# 00.net
KiCad netlist of a schematic drawn in Altium Designer
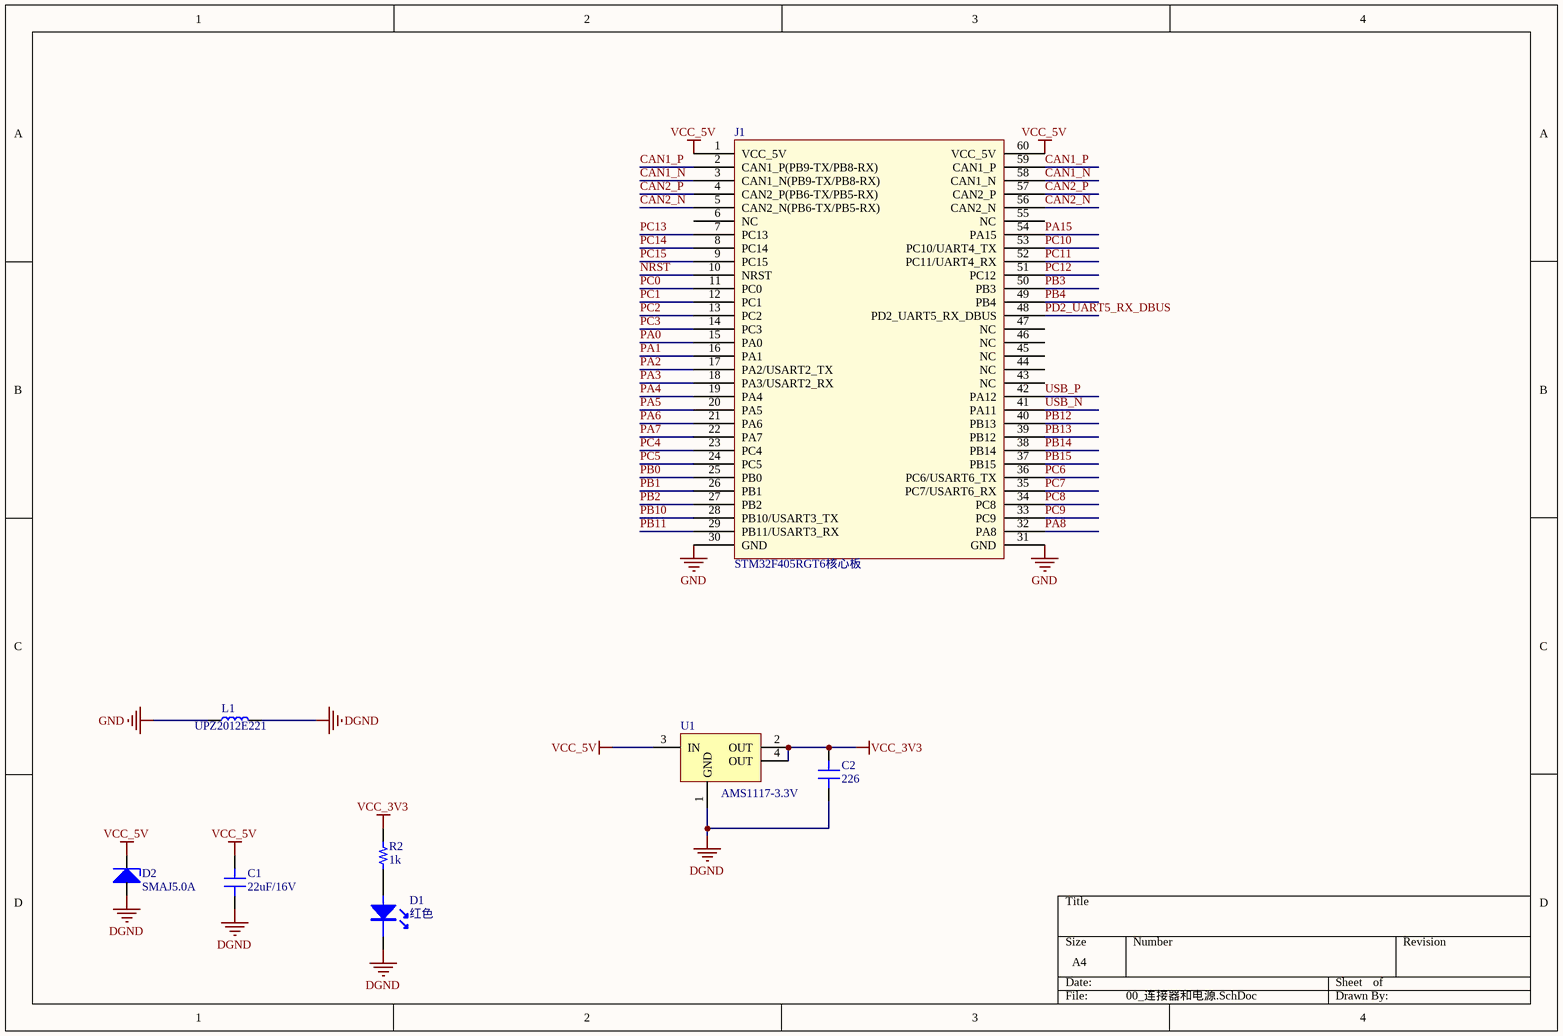
[diagram p0: 00_连接器和电源.SchDoc]

(export (version "E")
  (design (tool "Eeschema 10.0.6"))
  (components
    (comp (ref "C1")
      (value "22uF/16V")
      (footprint "C1206/3216")
      (description "陶瓷电容")
      (libsource (lib "WMJ2019_Devices") (part "陶瓷电容"))
    )
    (comp (ref "C2")
      (value "226")
      (footprint "C0603/1608")
      (description "陶瓷电容")
      (libsource (lib "WMJ2019_Devices") (part "陶瓷电容"))
    )
    (comp (ref "D1")
      (value "LED-红色")
      (footprint "LED0603-红色")
      (description "发光二极管")
      (fields (field (name "COLOR") "红色"))
      (libsource (lib "WMJ2019_Devices") (part "LED"))
    )
    (comp (ref "D2")
      (value "SMAJ5.0A")
      (footprint "DO-214AC/SMA")
      (description "瞬态抑制二极管")
      (libsource (lib "WMJ2019_Devices") (part "瞬态抑制二极管"))
    )
    (comp (ref "J1")
      (value "STM32F405RGT6核心板")
      (footprint "3710M060037G0FR01")
      (description "3710(F/M)060037G0FR01")
      (libsource (lib "Connectors") (part "STM32F405RGT6核心板"))
    )
    (comp (ref "L1")
      (value "UPZ2012E221")
      (footprint "L0805/2012")
      (description "贴片磁珠")
      (libsource (lib "WMJ2019_Devices") (part "磁珠"))
    )
    (comp (ref "R2")
      (value "1k")
      (footprint "R0603/1608")
      (description "电阻")
      (libsource (lib "WMJ2019_Devices") (part "电阻"))
    )
    (comp (ref "U1")
      (value "AMS1117-3.3V")
      (footprint "SOT-223")
      (description "AMS1117低压差线性稳压器")
      (libsource (lib "WMJ2019_Devices") (part "AMS1117"))
    )
  )
  (nets
    (net (code "1") (name "/CAN1_N") (class "Default")
      (node (ref "J1") (pin "3") (pinfunction "CAN1_N(PB9-TX/PB8-RX)_3") (pintype "passive"))
      (node (ref "J1") (pin "58") (pinfunction "CAN1_N_58") (pintype "passive"))
    )
    (net (code "2") (name "/CAN1_P") (class "Default")
      (node (ref "J1") (pin "2") (pinfunction "CAN1_P(PB9-TX/PB8-RX)_2") (pintype "passive"))
      (node (ref "J1") (pin "59") (pinfunction "CAN1_P_59") (pintype "passive"))
    )
    (net (code "3") (name "/CAN2_N") (class "Default")
      (node (ref "J1") (pin "5") (pinfunction "CAN2_N(PB6-TX/PB5-RX)_5") (pintype "passive"))
      (node (ref "J1") (pin "56") (pinfunction "CAN2_N_56") (pintype "passive"))
    )
    (net (code "4") (name "/CAN2_P") (class "Default")
      (node (ref "J1") (pin "4") (pinfunction "CAN2_P(PB6-TX/PB5-RX)_4") (pintype "passive"))
      (node (ref "J1") (pin "57") (pinfunction "CAN2_P_57") (pintype "passive"))
    )
    (net (code "5") (name "/NRST") (class "Default")
      (node (ref "J1") (pin "10") (pinfunction "NRST_10") (pintype "passive"))
    )
    (net (code "6") (name "/PA0") (class "Default")
      (node (ref "J1") (pin "15") (pinfunction "PA0_15") (pintype "passive"))
    )
    (net (code "7") (name "/PA1") (class "Default")
      (node (ref "J1") (pin "16") (pinfunction "PA1_16") (pintype "passive"))
    )
    (net (code "8") (name "/PA2") (class "Default")
      (node (ref "J1") (pin "17") (pinfunction "PA2/USART2_TX_17") (pintype "passive"))
    )
    (net (code "9") (name "/PA3") (class "Default")
      (node (ref "J1") (pin "18") (pinfunction "PA3/USART2_RX_18") (pintype "passive"))
    )
    (net (code "10") (name "/PA4") (class "Default")
      (node (ref "J1") (pin "19") (pinfunction "PA4_19") (pintype "passive"))
    )
    (net (code "11") (name "/PA5") (class "Default")
      (node (ref "J1") (pin "20") (pinfunction "PA5_20") (pintype "passive"))
    )
    (net (code "12") (name "/PA6") (class "Default")
      (node (ref "J1") (pin "21") (pinfunction "PA6_21") (pintype "passive"))
    )
    (net (code "13") (name "/PA7") (class "Default")
      (node (ref "J1") (pin "22") (pinfunction "PA7_22") (pintype "passive"))
    )
    (net (code "14") (name "/PA8") (class "Default")
      (node (ref "J1") (pin "32") (pinfunction "PA8_32") (pintype "passive"))
    )
    (net (code "15") (name "/PA15") (class "Default")
      (node (ref "J1") (pin "54") (pinfunction "PA15_54") (pintype "passive"))
    )
    (net (code "16") (name "/PB0") (class "Default")
      (node (ref "J1") (pin "25") (pinfunction "PB0_25") (pintype "passive"))
    )
    (net (code "17") (name "/PB1") (class "Default")
      (node (ref "J1") (pin "26") (pinfunction "PB1_26") (pintype "passive"))
    )
    (net (code "18") (name "/PB2") (class "Default")
      (node (ref "J1") (pin "27") (pinfunction "PB2_27") (pintype "passive"))
    )
    (net (code "19") (name "/PB3") (class "Default")
      (node (ref "J1") (pin "50") (pinfunction "PB3_50") (pintype "passive"))
    )
    (net (code "20") (name "/PB4") (class "Default")
      (node (ref "J1") (pin "49") (pinfunction "PB4_49") (pintype "passive"))
    )
    (net (code "21") (name "/PB10") (class "Default")
      (node (ref "J1") (pin "28") (pinfunction "PB10/USART3_TX_28") (pintype "passive"))
    )
    (net (code "22") (name "/PB11") (class "Default")
      (node (ref "J1") (pin "29") (pinfunction "PB11/USART3_RX_29") (pintype "passive"))
    )
    (net (code "23") (name "/PB12") (class "Default")
      (node (ref "J1") (pin "40") (pinfunction "PB13_40") (pintype "passive"))
    )
    (net (code "24") (name "/PB13") (class "Default")
      (node (ref "J1") (pin "39") (pinfunction "PB12_39") (pintype "passive"))
    )
    (net (code "25") (name "/PB14") (class "Default")
      (node (ref "J1") (pin "38") (pinfunction "PB14_38") (pintype "passive"))
    )
    (net (code "26") (name "/PB15") (class "Default")
      (node (ref "J1") (pin "37") (pinfunction "PB15_37") (pintype "passive"))
    )
    (net (code "27") (name "/PC0") (class "Default")
      (node (ref "J1") (pin "11") (pinfunction "PC0_11") (pintype "passive"))
    )
    (net (code "28") (name "/PC1") (class "Default")
      (node (ref "J1") (pin "12") (pinfunction "PC1_12") (pintype "passive"))
    )
    (net (code "29") (name "/PC2") (class "Default")
      (node (ref "J1") (pin "13") (pinfunction "PC2_13") (pintype "passive"))
    )
    (net (code "30") (name "/PC3") (class "Default")
      (node (ref "J1") (pin "14") (pinfunction "PC3_14") (pintype "passive"))
    )
    (net (code "31") (name "/PC4") (class "Default")
      (node (ref "J1") (pin "23") (pinfunction "PC4_23") (pintype "passive"))
    )
    (net (code "32") (name "/PC5") (class "Default")
      (node (ref "J1") (pin "24") (pinfunction "PC5_24") (pintype "passive"))
    )
    (net (code "33") (name "/PC6") (class "Default")
      (node (ref "J1") (pin "36") (pinfunction "PC6/USART6_TX_36") (pintype "passive"))
    )
    (net (code "34") (name "/PC7") (class "Default")
      (node (ref "J1") (pin "35") (pinfunction "PC7/USART6_RX_35") (pintype "passive"))
    )
    (net (code "35") (name "/PC8") (class "Default")
      (node (ref "J1") (pin "34") (pinfunction "PC8_34") (pintype "passive"))
    )
    (net (code "36") (name "/PC9") (class "Default")
      (node (ref "J1") (pin "33") (pinfunction "PC9_33") (pintype "passive"))
    )
    (net (code "37") (name "/PC10") (class "Default")
      (node (ref "J1") (pin "53") (pinfunction "PC10/UART4_TX_53") (pintype "passive"))
    )
    (net (code "38") (name "/PC11") (class "Default")
      (node (ref "J1") (pin "52") (pinfunction "PC11/UART4_RX_52") (pintype "passive"))
    )
    (net (code "39") (name "/PC12") (class "Default")
      (node (ref "J1") (pin "51") (pinfunction "PC12_51") (pintype "passive"))
    )
    (net (code "40") (name "/PC13") (class "Default")
      (node (ref "J1") (pin "7") (pinfunction "PC13_7") (pintype "passive"))
    )
    (net (code "41") (name "/PC14") (class "Default")
      (node (ref "J1") (pin "8") (pinfunction "PC14_8") (pintype "passive"))
    )
    (net (code "42") (name "/PC15") (class "Default")
      (node (ref "J1") (pin "9") (pinfunction "PC15_9") (pintype "passive"))
    )
    (net (code "43") (name "/PD2_UART5_RX_DBUS") (class "Default")
      (node (ref "J1") (pin "48") (pinfunction "PD2_UART5_RX_DBUS_48") (pintype "passive"))
    )
    (net (code "44") (name "/USB_N") (class "Default")
      (node (ref "J1") (pin "41") (pinfunction "PA11_41") (pintype "passive"))
    )
    (net (code "45") (name "/USB_P") (class "Default")
      (node (ref "J1") (pin "42") (pinfunction "PA12_42") (pintype "passive"))
    )
    (net (code "46") (name "DGND") (class "Default")
      (node (ref "C1") (pin "1") (pintype "passive"))
      (node (ref "C2") (pin "1") (pintype "passive"))
      (node (ref "D1") (pin "2") (pinfunction "K_2") (pintype "passive"))
      (node (ref "D2") (pin "1") (pinfunction "+_1") (pintype "passive"))
      (node (ref "L1") (pin "2") (pinfunction "2_2") (pintype "passive"))
      (node (ref "U1") (pin "1") (pinfunction "GND_1") (pintype "passive"))
    )
    (net (code "47") (name "GND") (class "Default")
      (node (ref "J1") (pin "30") (pinfunction "GND_30") (pintype "passive"))
      (node (ref "J1") (pin "31") (pinfunction "GND_31") (pintype "passive"))
      (node (ref "L1") (pin "1") (pinfunction "1_1") (pintype "passive"))
    )
    (net (code "48") (name "Net-(D1-A)") (class "Default")
      (node (ref "D1") (pin "1") (pinfunction "A_1") (pintype "passive"))
      (node (ref "R2") (pin "1") (pintype "passive"))
    )
    (net (code "49") (name "VCC_3V3") (class "Default")
      (node (ref "C2") (pin "2") (pintype "passive"))
      (node (ref "R2") (pin "2") (pintype "passive"))
      (node (ref "U1") (pin "2") (pinfunction "OUT_2") (pintype "passive"))
      (node (ref "U1") (pin "4") (pinfunction "OUT_4") (pintype "passive"))
    )
    (net (code "50") (name "VCC_5V") (class "Default")
      (node (ref "C1") (pin "2") (pintype "passive"))
      (node (ref "D2") (pin "2") (pinfunction "-_2") (pintype "passive"))
      (node (ref "J1") (pin "1") (pinfunction "VCC_5V_1") (pintype "passive"))
      (node (ref "J1") (pin "60") (pinfunction "VCC_5V_60") (pintype "passive"))
      (node (ref "U1") (pin "3") (pinfunction "IN_3") (pintype "passive"))
    )
    (net (code "51") (name "unconnected-(J1-NC-Pad6)") (class "Default")
      (node (ref "J1") (pin "6") (pinfunction "NC_6") (pintype "passive"))
    )
    (net (code "52") (name "unconnected-(J1-NC-Pad43)") (class "Default")
      (node (ref "J1") (pin "43") (pinfunction "NC_43") (pintype "passive"))
    )
    (net (code "53") (name "unconnected-(J1-NC-Pad44)") (class "Default")
      (node (ref "J1") (pin "44") (pinfunction "NC_44") (pintype "passive"))
    )
    (net (code "54") (name "unconnected-(J1-NC-Pad45)") (class "Default")
      (node (ref "J1") (pin "45") (pinfunction "NC_45") (pintype "passive"))
    )
    (net (code "55") (name "unconnected-(J1-NC-Pad46)") (class "Default")
      (node (ref "J1") (pin "46") (pinfunction "NC_46") (pintype "passive"))
    )
    (net (code "56") (name "unconnected-(J1-NC-Pad47)") (class "Default")
      (node (ref "J1") (pin "47") (pinfunction "NC_47") (pintype "passive"))
    )
    (net (code "57") (name "unconnected-(J1-NC-Pad55)") (class "Default")
      (node (ref "J1") (pin "55") (pinfunction "NC_55") (pintype "passive"))
    )
  )
)
